# crystalis.net
KiCad netlist of a schematic drawn in EAGLE
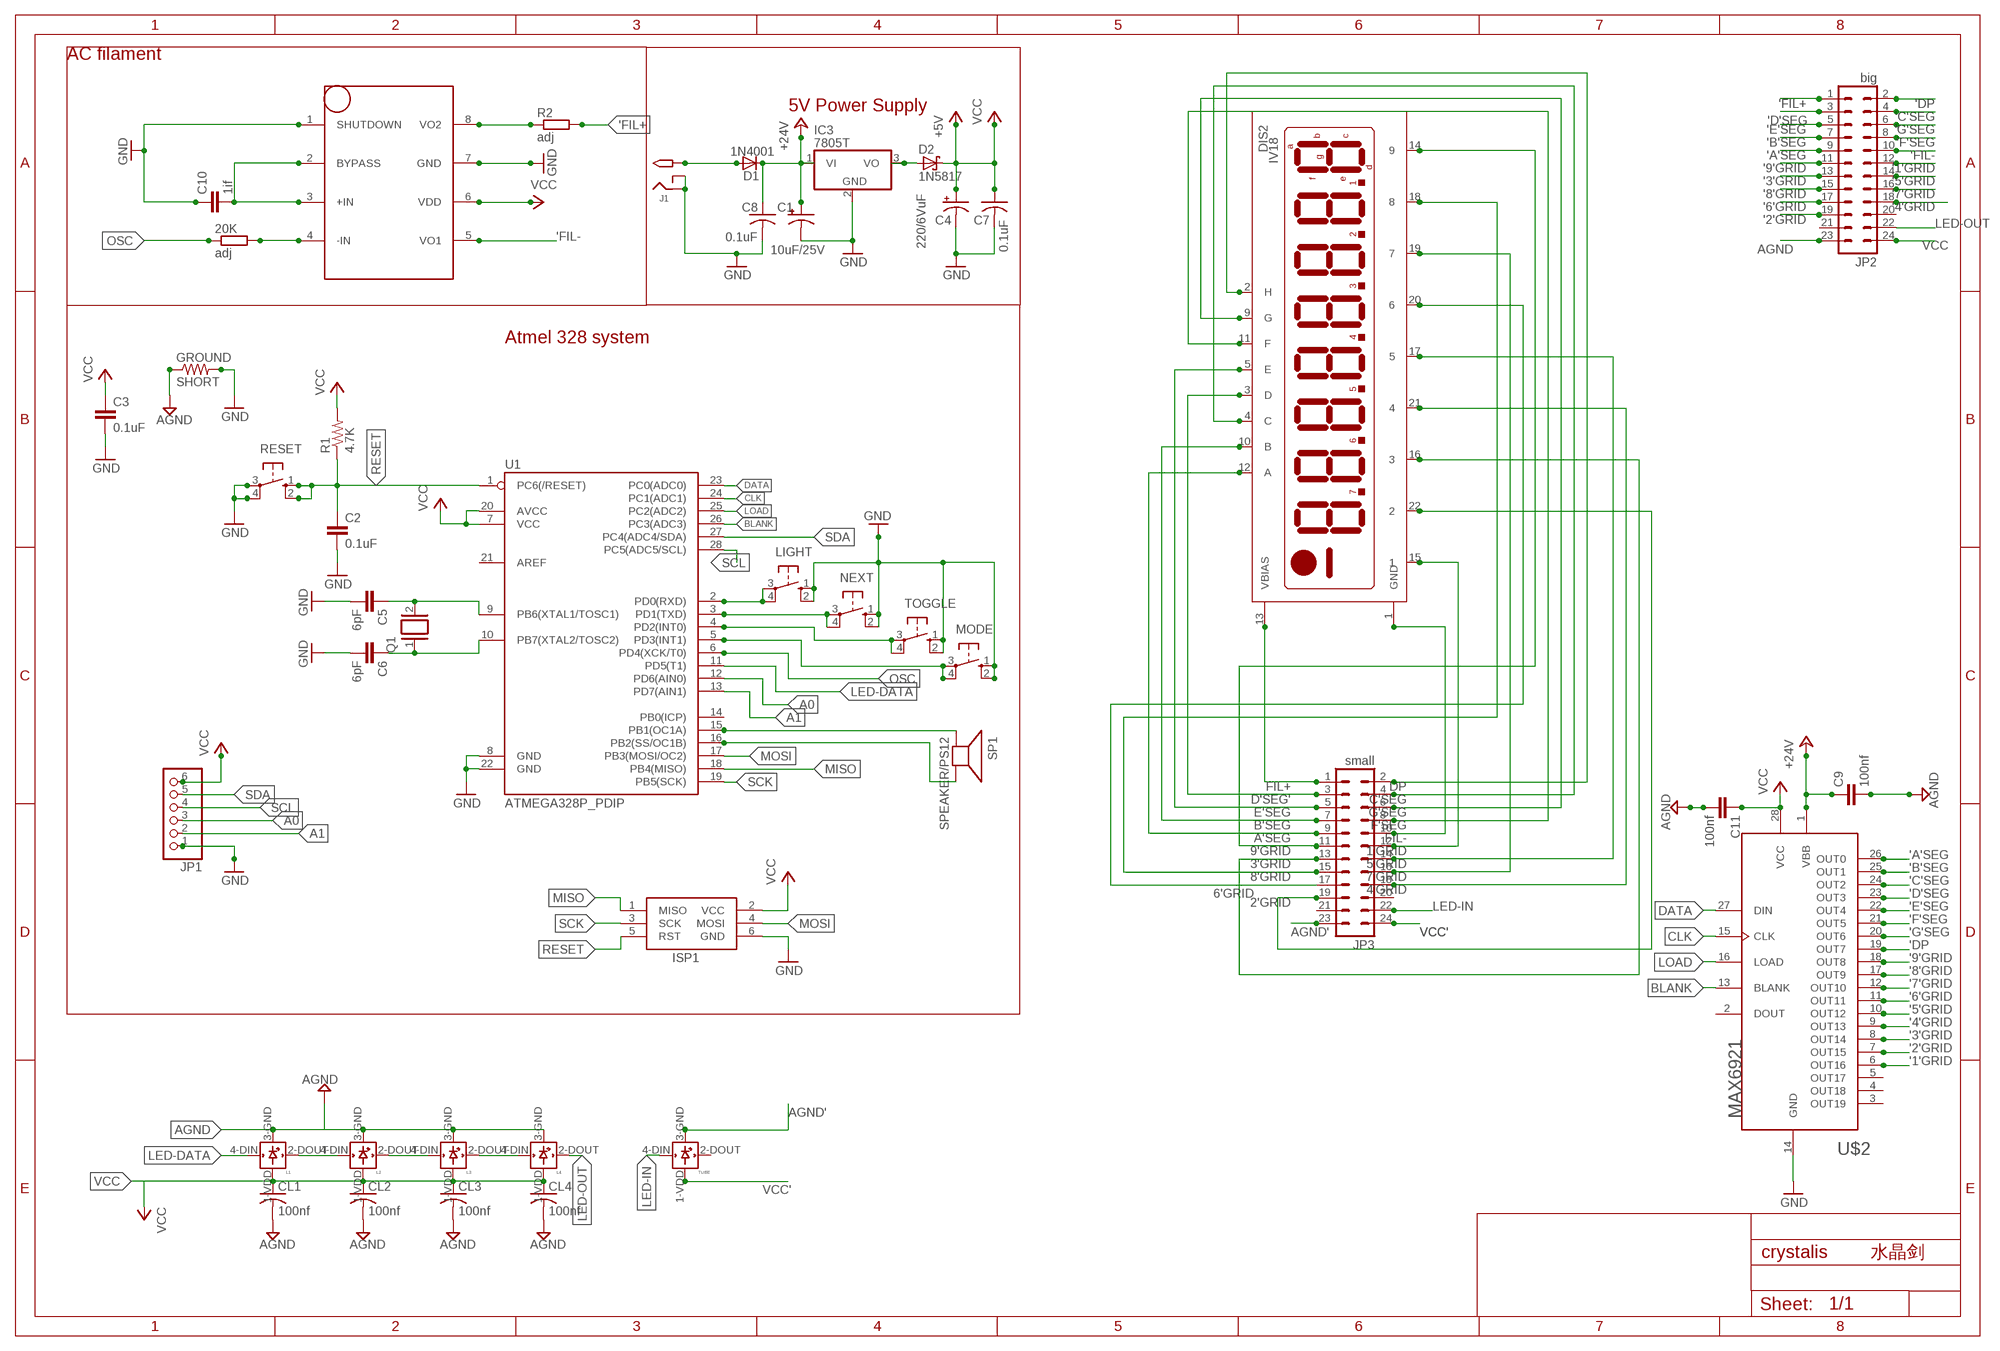
[diagram p0: schematic, sheet 1]

(export (version "E")
  (design (tool "Eeschema 10.0.6"))
  (components
    (comp (ref "20K")
      (value "adj")
      (footprint "eagle-import:0207_5V")
      (libsource (lib "eagle-import") (part "R-EU_0207/5V"))
    )
    (comp (ref "C1")
      (value "10uF/25V")
      (footprint "eagle-import:E2,5-6")
      (libsource (lib "eagle-import") (part "CPOL-USE2.5-6"))
    )
    (comp (ref "C2")
      (value "0.1uF")
      (footprint "eagle-import:C025-025X050")
      (libsource (lib "eagle-import") (part "C-EU025-025X050"))
    )
    (comp (ref "C3")
      (value "0.1uF")
      (footprint "eagle-import:C025-025X050")
      (libsource (lib "eagle-import") (part "C-EU025-025X050"))
    )
    (comp (ref "C4")
      (value "220/6VuF")
      (footprint "eagle-import:E2,5-6")
      (libsource (lib "eagle-import") (part "CPOL-USE2.5-6"))
    )
    (comp (ref "C5")
      (value "6pF")
      (footprint "eagle-import:C025-024X044")
      (libsource (lib "eagle-import") (part "C-EU025-024X044"))
    )
    (comp (ref "C6")
      (value "6pF")
      (footprint "eagle-import:C025-024X044")
      (libsource (lib "eagle-import") (part "C-EU025-024X044"))
    )
    (comp (ref "C7")
      (value "0.1uF")
      (footprint "eagle-import:C025-025X050")
      (libsource (lib "eagle-import") (part "C-US025-025X050"))
    )
    (comp (ref "C8")
      (value "0.1uF")
      (footprint "eagle-import:C025-025X050")
      (libsource (lib "eagle-import") (part "C-US025-025X050"))
    )
    (comp (ref "C9")
      (value "100nf")
      (footprint "eagle-import:C050-030X075")
      (libsource (lib "eagle-import") (part "C-EU050-030X075"))
    )
    (comp (ref "C10")
      (value "1if")
      (footprint "eagle-import:C025-030X050")
      (libsource (lib "eagle-import") (part "C-EU025-030X050"))
    )
    (comp (ref "C11")
      (value "100nf")
      (footprint "eagle-import:C050-030X075")
      (libsource (lib "eagle-import") (part "C-EU050-030X075"))
    )
    (comp (ref "CL1")
      (value "100nf")
      (footprint "eagle-import:C1206")
      (libsource (lib "eagle-import") (part "rcl_C-USC1206"))
    )
    (comp (ref "CL2")
      (value "100nf")
      (footprint "eagle-import:C1206")
      (libsource (lib "eagle-import") (part "rcl_C-USC1206"))
    )
    (comp (ref "CL3")
      (value "100nf")
      (footprint "eagle-import:C1206")
      (libsource (lib "eagle-import") (part "rcl_C-USC1206"))
    )
    (comp (ref "CL4")
      (value "100nf")
      (footprint "eagle-import:C1206")
      (libsource (lib "eagle-import") (part "rcl_C-USC1206"))
    )
    (comp (ref "D1")
      (value "1N4001")
      (footprint "eagle-import:DO41-10")
      (libsource (lib "eagle-import") (part "1N4004"))
    )
    (comp (ref "D2")
      (value "1N5817")
      (footprint "eagle-import:DO41-10")
      (libsource (lib "eagle-import") (part "SCHOTTKY-DIODEDO41"))
    )
    (comp (ref "DIS2")
      (value "IV18")
      (footprint "eagle-import:IV18")
      (libsource (lib "eagle-import") (part "IV18"))
    )
    (comp (ref "GROUND")
      (value "SHORT")
      (footprint "eagle-import:M1206")
      (libsource (lib "eagle-import") (part "R-US_M1206"))
    )
    (comp (ref "IC3")
      (value "7805T")
      (footprint "eagle-import:TO220H")
      (libsource (lib "eagle-import") (part "78T05"))
    )
    (comp (ref "ISP1")
      (value "AVRISP-6")
      (footprint "eagle-import:AVRISP")
      (libsource (lib "eagle-import") (part "AVRISP-6"))
    )
    (comp (ref "J1")
      (value "2.1MMJACK")
      (footprint "eagle-import:PJ-102A")
      (libsource (lib "eagle-import") (part "2.1MMJACK"))
    )
    (comp (ref "JP1")
      (value "PINHD-1X6")
      (footprint "eagle-import:1X06")
      (libsource (lib "eagle-import") (part "PINHD-1X6"))
    )
    (comp (ref "JP2")
      (value "big")
      (footprint "eagle-import:MA12-2")
      (libsource (lib "eagle-import") (part "MA12-2"))
    )
    (comp (ref "JP3")
      (value "small")
      (footprint "eagle-import:MA12-2")
      (libsource (lib "eagle-import") (part "MA12-2"))
    )
    (comp (ref "L1")
      (value "WS2812B")
      (footprint "eagle-import:WS2812B")
      (libsource (lib "eagle-import") (part "WS2812B"))
    )
    (comp (ref "L2")
      (value "WS2812B")
      (footprint "eagle-import:WS2812B")
      (libsource (lib "eagle-import") (part "WS2812B"))
    )
    (comp (ref "L3")
      (value "WS2812B")
      (footprint "eagle-import:WS2812B")
      (libsource (lib "eagle-import") (part "WS2812B"))
    )
    (comp (ref "L4")
      (value "WS2812B")
      (footprint "eagle-import:WS2812B")
      (libsource (lib "eagle-import") (part "WS2812B"))
    )
    (comp (ref "LIGHT")
      (value "40-XX")
      (footprint "eagle-import:B3F-40XX")
      (fields (field (name "MF") "OMRON COMPONENTS USA") (field (name "MPN") "B3F-4000"))
      (libsource (lib "eagle-import") (part "40-XX"))
    )
    (comp (ref "MODE")
      (value "40-XX")
      (footprint "eagle-import:B3F-40XX")
      (fields (field (name "MF") "OMRON COMPONENTS USA") (field (name "MPN") "B3F-4000"))
      (libsource (lib "eagle-import") (part "40-XX"))
    )
    (comp (ref "NEXT")
      (value "40-XX")
      (footprint "eagle-import:B3F-40XX")
      (fields (field (name "MF") "OMRON COMPONENTS USA") (field (name "MPN") "B3F-4000"))
      (libsource (lib "eagle-import") (part "40-XX"))
    )
    (comp (ref "Q1")
      (value "XTAL/S")
      (footprint "eagle-import:QS")
      (libsource (lib "eagle-import") (part "XTAL/S"))
    )
    (comp (ref "R1")
      (value "4.7K")
      (footprint "eagle-import:0309_12")
      (libsource (lib "eagle-import") (part "R-US_0309/12"))
    )
    (comp (ref "R2")
      (value "adj")
      (footprint "eagle-import:0207_5V")
      (libsource (lib "eagle-import") (part "R-EU_0207/5V"))
    )
    (comp (ref "RESET")
      (value "10-XX")
      (footprint "eagle-import:B3F-10XX")
      (fields (field (name "MPN") "B3F-1000"))
      (libsource (lib "eagle-import") (part "10-XX"))
    )
    (comp (ref "SP1")
      (value "SPEAKER/PS12")
      (footprint "eagle-import:PS12")
      (libsource (lib "eagle-import") (part "SPEAKER/PS12"))
    )
    (comp (ref "TOGGLE")
      (value "40-XX")
      (footprint "eagle-import:B3F-40XX")
      (fields (field (name "MF") "OMRON COMPONENTS USA") (field (name "MPN") "B3F-4000"))
      (libsource (lib "eagle-import") (part "40-XX"))
    )
    (comp (ref "TUBE")
      (value "WS2812B")
      (footprint "eagle-import:WS2812B")
      (libsource (lib "eagle-import") (part "WS2812B"))
    )
    (comp (ref "U$1")
      (value "LM4871")
      (footprint "eagle-import:SO08")
      (libsource (lib "eagle-import") (part "LM4871"))
    )
    (comp (ref "U$2")
      (value "MAX6921")
      (footprint "eagle-import:PLCC-S28")
      (libsource (lib "eagle-import") (part "MAX6921"))
    )
    (comp (ref "U1")
      (value "ATMEGA328P_PDIP")
      (footprint "eagle-import:DIL28-3")
      (libsource (lib "eagle-import") (part "ATMEGA328P_PDIP"))
    )
  )
  (nets
    (net (code "1") (name "'FIL+") (class "Default")
      (node (ref "JP2") (pin "1") (pinfunction "1_1") (pintype "passive"))
      (node (ref "R2") (pin "2") (pinfunction "2_2") (pintype "passive"))
    )
    (net (code "2") (name "+24V") (class "Default")
      (node (ref "C1") (pin "+") (pinfunction "+_+") (pintype "passive"))
      (node (ref "C8") (pin "1") (pinfunction "1_1") (pintype "passive"))
      (node (ref "C9") (pin "1") (pinfunction "1_1") (pintype "passive"))
      (node (ref "D1") (pin "C") (pinfunction "C_C") (pintype "passive"))
      (node (ref "IC3") (pin "1") (pinfunction "VI_1") (pintype "input"))
      (node (ref "U$2") (pin "1") (pinfunction "VBB_1") (pintype "power_in"))
    )
    (net (code "3") (name "/'1'GRID") (class "Default")
      (node (ref "JP2") (pin "12") (pinfunction "12_12") (pintype "passive"))
      (node (ref "U$2") (pin "6") (pinfunction "OUT16_6") (pintype "output"))
    )
    (net (code "4") (name "/'2'GRID") (class "Default")
      (node (ref "JP2") (pin "19") (pinfunction "19_19") (pintype "passive"))
      (node (ref "U$2") (pin "7") (pinfunction "OUT15_7") (pintype "output"))
    )
    (net (code "5") (name "/'3'GRID") (class "Default")
      (node (ref "JP2") (pin "13") (pinfunction "13_13") (pintype "passive"))
      (node (ref "U$2") (pin "8") (pinfunction "OUT14_8") (pintype "output"))
    )
    (net (code "6") (name "/'4'GRID") (class "Default")
      (node (ref "JP2") (pin "18") (pinfunction "18_18") (pintype "passive"))
      (node (ref "U$2") (pin "9") (pinfunction "OUT13_9") (pintype "output"))
    )
    (net (code "7") (name "/'5'GRID") (class "Default")
      (node (ref "JP2") (pin "14") (pinfunction "14_14") (pintype "passive"))
      (node (ref "U$2") (pin "10") (pinfunction "OUT12_10") (pintype "output"))
    )
    (net (code "8") (name "/'6'GRID") (class "Default")
      (node (ref "JP2") (pin "17") (pinfunction "17_17") (pintype "passive"))
      (node (ref "U$2") (pin "11") (pinfunction "OUT11_11") (pintype "output"))
    )
    (net (code "9") (name "/'7'GRID") (class "Default")
      (node (ref "JP2") (pin "16") (pinfunction "16_16") (pintype "passive"))
      (node (ref "U$2") (pin "12") (pinfunction "OUT10_12") (pintype "output"))
    )
    (net (code "10") (name "/'8'GRID") (class "Default")
      (node (ref "JP2") (pin "15") (pinfunction "15_15") (pintype "passive"))
      (node (ref "U$2") (pin "17") (pinfunction "OUT9_17") (pintype "output"))
    )
    (net (code "11") (name "/'9'GRID") (class "Default")
      (node (ref "JP2") (pin "11") (pinfunction "11_11") (pintype "passive"))
      (node (ref "U$2") (pin "18") (pinfunction "OUT8_18") (pintype "output"))
    )
    (net (code "12") (name "/'A'SEG") (class "Default")
      (node (ref "JP2") (pin "9") (pinfunction "9_9") (pintype "passive"))
      (node (ref "U$2") (pin "26") (pinfunction "OUT0_26") (pintype "output"))
    )
    (net (code "13") (name "/'B'SEG") (class "Default")
      (node (ref "JP2") (pin "7") (pinfunction "7_7") (pintype "passive"))
      (node (ref "U$2") (pin "25") (pinfunction "OUT1_25") (pintype "output"))
    )
    (net (code "14") (name "/'C'SEG") (class "Default")
      (node (ref "JP2") (pin "4") (pinfunction "4_4") (pintype "passive"))
      (node (ref "U$2") (pin "24") (pinfunction "OUT2_24") (pintype "output"))
    )
    (net (code "15") (name "/'D'SEG") (class "Default")
      (node (ref "JP2") (pin "3") (pinfunction "3_3") (pintype "passive"))
      (node (ref "U$2") (pin "23") (pinfunction "OUT3_23") (pintype "output"))
    )
    (net (code "16") (name "/'DP") (class "Default")
      (node (ref "JP2") (pin "2") (pinfunction "2_2") (pintype "passive"))
      (node (ref "U$2") (pin "19") (pinfunction "OUT7_19") (pintype "output"))
    )
    (net (code "17") (name "/'E'SEG") (class "Default")
      (node (ref "JP2") (pin "5") (pinfunction "5_5") (pintype "passive"))
      (node (ref "U$2") (pin "22") (pinfunction "OUT4_22") (pintype "output"))
    )
    (net (code "18") (name "/'F'SEG") (class "Default")
      (node (ref "JP2") (pin "8") (pinfunction "8_8") (pintype "passive"))
      (node (ref "U$2") (pin "21") (pinfunction "OUT5_21") (pintype "output"))
    )
    (net (code "19") (name "/'FIL-") (class "Default")
      (node (ref "JP2") (pin "10") (pinfunction "10_10") (pintype "passive"))
      (node (ref "U$1") (pin "5") (pinfunction "VO1_5") (pintype "bidirectional"))
    )
    (net (code "20") (name "/'G'SEG") (class "Default")
      (node (ref "JP2") (pin "6") (pinfunction "6_6") (pintype "passive"))
      (node (ref "U$2") (pin "20") (pinfunction "OUT6_20") (pintype "output"))
    )
    (net (code "21") (name "/1'GRID") (class "Default")
      (node (ref "DIS2") (pin "15") (pinfunction "1_15") (pintype "passive"))
      (node (ref "JP3") (pin "12") (pinfunction "12_12") (pintype "passive"))
    )
    (net (code "22") (name "/2'GRID") (class "Default")
      (node (ref "DIS2") (pin "22") (pinfunction "2_22") (pintype "passive"))
      (node (ref "JP3") (pin "19") (pinfunction "19_19") (pintype "passive"))
    )
    (net (code "23") (name "/3'GRID") (class "Default")
      (node (ref "DIS2") (pin "16") (pinfunction "3_16") (pintype "passive"))
      (node (ref "JP3") (pin "13") (pinfunction "13_13") (pintype "passive"))
    )
    (net (code "24") (name "/4'GRID") (class "Default")
      (node (ref "DIS2") (pin "21") (pinfunction "4_21") (pintype "passive"))
      (node (ref "JP3") (pin "18") (pinfunction "18_18") (pintype "passive"))
    )
    (net (code "25") (name "/5'GRID") (class "Default")
      (node (ref "DIS2") (pin "17") (pinfunction "5_17") (pintype "passive"))
      (node (ref "JP3") (pin "14") (pinfunction "14_14") (pintype "passive"))
    )
    (net (code "26") (name "/6'GRID") (class "Default")
      (node (ref "DIS2") (pin "20") (pinfunction "6_20") (pintype "passive"))
      (node (ref "JP3") (pin "17") (pinfunction "17_17") (pintype "passive"))
    )
    (net (code "27") (name "/7'GRID") (class "Default")
      (node (ref "DIS2") (pin "19") (pinfunction "7_19") (pintype "passive"))
      (node (ref "JP3") (pin "16") (pinfunction "16_16") (pintype "passive"))
    )
    (net (code "28") (name "/8'GRID") (class "Default")
      (node (ref "DIS2") (pin "18") (pinfunction "8_18") (pintype "passive"))
      (node (ref "JP3") (pin "15") (pinfunction "15_15") (pintype "passive"))
    )
    (net (code "29") (name "/9'GRID") (class "Default")
      (node (ref "DIS2") (pin "14") (pinfunction "9_14") (pintype "passive"))
      (node (ref "JP3") (pin "11") (pinfunction "11_11") (pintype "passive"))
    )
    (net (code "30") (name "/A'SEG") (class "Default")
      (node (ref "DIS2") (pin "12") (pinfunction "A_12") (pintype "passive"))
      (node (ref "JP3") (pin "9") (pinfunction "9_9") (pintype "passive"))
    )
    (net (code "31") (name "/AGND'") (class "Default")
      (node (ref "JP3") (pin "23") (pinfunction "23_23") (pintype "passive"))
      (node (ref "TUBE") (pin "3-GND") (pinfunction "GND_3-GND") (pintype "bidirectional"))
    )
    (net (code "32") (name "/B'SEG") (class "Default")
      (node (ref "DIS2") (pin "10") (pinfunction "B_10") (pintype "passive"))
      (node (ref "JP3") (pin "7") (pinfunction "7_7") (pintype "passive"))
    )
    (net (code "33") (name "/C'SEG") (class "Default")
      (node (ref "DIS2") (pin "4") (pinfunction "C_4") (pintype "passive"))
      (node (ref "JP3") (pin "4") (pinfunction "4_4") (pintype "passive"))
    )
    (net (code "34") (name "/D'SEG'") (class "Default")
      (node (ref "DIS2") (pin "3") (pinfunction "D_3") (pintype "passive"))
      (node (ref "JP3") (pin "3") (pinfunction "3_3") (pintype "passive"))
    )
    (net (code "35") (name "/DP") (class "Default")
      (node (ref "DIS2") (pin "2") (pinfunction "H_2") (pintype "passive"))
      (node (ref "JP3") (pin "2") (pinfunction "2_2") (pintype "passive"))
    )
    (net (code "36") (name "/E'SEG") (class "Default")
      (node (ref "DIS2") (pin "5") (pinfunction "E_5") (pintype "passive"))
      (node (ref "JP3") (pin "5") (pinfunction "5_5") (pintype "passive"))
    )
    (net (code "37") (name "/F'SEG") (class "Default")
      (node (ref "DIS2") (pin "11") (pinfunction "F_11") (pintype "passive"))
      (node (ref "JP3") (pin "8") (pinfunction "8_8") (pintype "passive"))
    )
    (net (code "38") (name "/FIL+") (class "Default")
      (node (ref "DIS2") (pin "13") (pinfunction "VBIAS_13") (pintype "power_in"))
      (node (ref "JP3") (pin "1") (pinfunction "1_1") (pintype "passive"))
    )
    (net (code "39") (name "/FIL-") (class "Default")
      (node (ref "DIS2") (pin "1") (pinfunction "GND_1") (pintype "power_in"))
      (node (ref "JP3") (pin "10") (pinfunction "10_10") (pintype "passive"))
    )
    (net (code "40") (name "/G'SEG") (class "Default")
      (node (ref "DIS2") (pin "9") (pinfunction "G_9") (pintype "passive"))
      (node (ref "JP3") (pin "6") (pinfunction "6_6") (pintype "passive"))
    )
    (net (code "41") (name "/VCC'") (class "Default")
      (node (ref "JP3") (pin "24") (pinfunction "24_24") (pintype "passive"))
      (node (ref "TUBE") (pin "1-VDD") (pinfunction "VDD_1-VDD") (pintype "bidirectional"))
    )
    (net (code "42") (name "A0") (class "Default")
      (node (ref "JP1") (pin "3") (pinfunction "3_3") (pintype "passive"))
      (node (ref "U1") (pin "12") (pinfunction "PD6(AIN0)_12") (pintype "bidirectional"))
    )
    (net (code "43") (name "A1") (class "Default")
      (node (ref "JP1") (pin "2") (pinfunction "2_2") (pintype "passive"))
      (node (ref "U1") (pin "13") (pinfunction "PD7(AIN1)_13") (pintype "bidirectional"))
    )
    (net (code "44") (name "AGND") (class "Default")
      (node (ref "C11") (pin "2") (pinfunction "2_2") (pintype "passive"))
      (node (ref "C9") (pin "2") (pinfunction "2_2") (pintype "passive"))
      (node (ref "CL1") (pin "2") (pinfunction "2_2") (pintype "passive"))
      (node (ref "CL2") (pin "2") (pinfunction "2_2") (pintype "passive"))
      (node (ref "CL3") (pin "2") (pinfunction "2_2") (pintype "passive"))
      (node (ref "CL4") (pin "2") (pinfunction "2_2") (pintype "passive"))
      (node (ref "GROUND") (pin "1") (pinfunction "1_1") (pintype "passive"))
      (node (ref "JP2") (pin "23") (pinfunction "23_23") (pintype "passive"))
      (node (ref "L1") (pin "3-GND") (pinfunction "GND_3-GND") (pintype "bidirectional"))
      (node (ref "L2") (pin "3-GND") (pinfunction "GND_3-GND") (pintype "bidirectional"))
      (node (ref "L3") (pin "3-GND") (pinfunction "GND_3-GND") (pintype "bidirectional"))
      (node (ref "L4") (pin "3-GND") (pinfunction "GND_3-GND") (pintype "bidirectional"))
    )
    (net (code "45") (name "BLANK") (class "Default")
      (node (ref "U$2") (pin "13") (pinfunction "BLANK_13") (pintype "input"))
      (node (ref "U1") (pin "26") (pinfunction "PC3(ADC3)_26") (pintype "bidirectional"))
    )
    (net (code "46") (name "CLK") (class "Default")
      (node (ref "U$2") (pin "15") (pinfunction "CLK_15") (pintype "input"))
      (node (ref "U1") (pin "24") (pinfunction "PC1(ADC1)_24") (pintype "bidirectional"))
    )
    (net (code "47") (name "DATA") (class "Default")
      (node (ref "U$2") (pin "27") (pinfunction "DIN_27") (pintype "input"))
      (node (ref "U1") (pin "23") (pinfunction "PC0(ADC0)_23") (pintype "bidirectional"))
    )
    (net (code "48") (name "GND") (class "Default")
      (node (ref "C1") (pin "-") (pinfunction "-_-") (pintype "passive"))
      (node (ref "C10") (pin "1") (pinfunction "1_1") (pintype "passive"))
      (node (ref "C2") (pin "2") (pinfunction "2_2") (pintype "passive"))
      (node (ref "C3") (pin "2") (pinfunction "2_2") (pintype "passive"))
      (node (ref "C4") (pin "-") (pinfunction "-_-") (pintype "passive"))
      (node (ref "C5") (pin "2") (pinfunction "2_2") (pintype "passive"))
      (node (ref "C6") (pin "2") (pinfunction "2_2") (pintype "passive"))
      (node (ref "C7") (pin "2") (pinfunction "2_2") (pintype "passive"))
      (node (ref "C8") (pin "2") (pinfunction "2_2") (pintype "passive"))
      (node (ref "GROUND") (pin "2") (pinfunction "2_2") (pintype "passive"))
      (node (ref "IC3") (pin "2") (pinfunction "GND_2") (pintype "passive"))
      (node (ref "ISP1") (pin "6") (pinfunction "GND_6") (pintype "power_in"))
      (node (ref "J1") (pin "RING") (pinfunction "RING_RING") (pintype "bidirectional"))
      (node (ref "J1") (pin "RING_SW") (pinfunction "RING_SW_RING_SW") (pintype "bidirectional"))
      (node (ref "JP1") (pin "1") (pinfunction "1_1") (pintype "passive"))
      (node (ref "LIGHT") (pin "1") (pinfunction "S_1") (pintype "passive"))
      (node (ref "LIGHT") (pin "2") (pinfunction "S1_2") (pintype "passive"))
      (node (ref "MODE") (pin "1") (pinfunction "S_1") (pintype "passive"))
      (node (ref "MODE") (pin "2") (pinfunction "S1_2") (pintype "passive"))
      (node (ref "NEXT") (pin "1") (pinfunction "S_1") (pintype "passive"))
      (node (ref "NEXT") (pin "2") (pinfunction "S1_2") (pintype "passive"))
      (node (ref "RESET") (pin "3") (pinfunction "P_3") (pintype "passive"))
      (node (ref "RESET") (pin "4") (pinfunction "P1_4") (pintype "passive"))
      (node (ref "TOGGLE") (pin "1") (pinfunction "S_1") (pintype "passive"))
      (node (ref "TOGGLE") (pin "2") (pinfunction "S1_2") (pintype "passive"))
      (node (ref "U$1") (pin "1") (pinfunction "SHUTDOWN_1") (pintype "bidirectional"))
      (node (ref "U$1") (pin "7") (pinfunction "GND_7") (pintype "bidirectional"))
      (node (ref "U$2") (pin "14") (pinfunction "GND_14") (pintype "power_in"))
      (node (ref "U1") (pin "22") (pinfunction "GND_22") (pintype "bidirectional"))
      (node (ref "U1") (pin "8") (pinfunction "GND_8") (pintype "bidirectional"))
    )
    (net (code "49") (name "LED-DATA") (class "Default")
      (node (ref "L1") (pin "4-DIN") (pinfunction "DIN_4-DIN") (pintype "input"))
      (node (ref "U1") (pin "11") (pinfunction "PD5(T1)_11") (pintype "bidirectional"))
    )
    (net (code "50") (name "LED-IN") (class "Default")
      (node (ref "JP3") (pin "22") (pinfunction "22_22") (pintype "passive"))
      (node (ref "TUBE") (pin "4-DIN") (pinfunction "DIN_4-DIN") (pintype "input"))
    )
    (net (code "51") (name "LED-OUT") (class "Default")
      (node (ref "JP2") (pin "22") (pinfunction "22_22") (pintype "passive"))
      (node (ref "L4") (pin "2-DOUT") (pinfunction "DOUT_2-DOUT") (pintype "output"))
    )
    (net (code "52") (name "LOAD") (class "Default")
      (node (ref "U$2") (pin "16") (pinfunction "LOAD_16") (pintype "input"))
      (node (ref "U1") (pin "25") (pinfunction "PC2(ADC2)_25") (pintype "bidirectional"))
    )
    (net (code "53") (name "MISO") (class "Default")
      (node (ref "ISP1") (pin "1") (pinfunction "MISO_1") (pintype "input"))
      (node (ref "U1") (pin "18") (pinfunction "PB4(MISO)_18") (pintype "bidirectional"))
    )
    (net (code "54") (name "MOSI") (class "Default")
      (node (ref "ISP1") (pin "4") (pinfunction "MOSI_4") (pintype "output"))
      (node (ref "U1") (pin "17") (pinfunction "PB3(MOSI/OC2)_17") (pintype "bidirectional"))
    )
    (net (code "55") (name "Net-(D1-PadA)") (class "Default")
      (node (ref "D1") (pin "A") (pinfunction "A_A") (pintype "passive"))
      (node (ref "J1") (pin "TIP") (pinfunction "TIP_TIP") (pintype "bidirectional"))
    )
    (net (code "56") (name "Net-(IC3-VO)") (class "Default")
      (node (ref "D2") (pin "A") (pinfunction "A_A") (pintype "passive"))
      (node (ref "IC3") (pin "3") (pinfunction "VO_3") (pintype "passive"))
    )
    (net (code "57") (name "Net-(L1-DOUT)") (class "Default")
      (node (ref "L1") (pin "2-DOUT") (pinfunction "DOUT_2-DOUT") (pintype "output"))
      (node (ref "L2") (pin "4-DIN") (pinfunction "DIN_4-DIN") (pintype "input"))
    )
    (net (code "58") (name "Net-(L2-DOUT)") (class "Default")
      (node (ref "L2") (pin "2-DOUT") (pinfunction "DOUT_2-DOUT") (pintype "output"))
      (node (ref "L3") (pin "4-DIN") (pinfunction "DIN_4-DIN") (pintype "input"))
    )
    (net (code "59") (name "Net-(L3-DOUT)") (class "Default")
      (node (ref "L3") (pin "2-DOUT") (pinfunction "DOUT_2-DOUT") (pintype "output"))
      (node (ref "L4") (pin "4-DIN") (pinfunction "DIN_4-DIN") (pintype "input"))
    )
    (net (code "60") (name "Net-(LIGHT-P)") (class "Default")
      (node (ref "LIGHT") (pin "3") (pinfunction "P_3") (pintype "passive"))
      (node (ref "LIGHT") (pin "4") (pinfunction "P1_4") (pintype "passive"))
      (node (ref "U1") (pin "2") (pinfunction "PD0(RXD)_2") (pintype "bidirectional"))
    )
    (net (code "61") (name "Net-(MODE-P)") (class "Default")
      (node (ref "MODE") (pin "3") (pinfunction "P_3") (pintype "passive"))
      (node (ref "MODE") (pin "4") (pinfunction "P1_4") (pintype "passive"))
      (node (ref "U1") (pin "5") (pinfunction "PD3(INT1)_5") (pintype "bidirectional"))
    )
    (net (code "62") (name "Net-(NEXT-P)") (class "Default")
      (node (ref "NEXT") (pin "3") (pinfunction "P_3") (pintype "passive"))
      (node (ref "NEXT") (pin "4") (pinfunction "P1_4") (pintype "passive"))
      (node (ref "U1") (pin "3") (pinfunction "PD1(TXD)_3") (pintype "bidirectional"))
    )
    (net (code "63") (name "Net-(SP1-+)") (class "Default")
      (node (ref "SP1") (pin "P$1") (pinfunction "+_P$1") (pintype "passive"))
      (node (ref "U1") (pin "15") (pinfunction "PB1(OC1A)_15") (pintype "bidirectional"))
    )
    (net (code "64") (name "Net-(SP1--)") (class "Default")
      (node (ref "SP1") (pin "P$2") (pinfunction "-_P$2") (pintype "passive"))
      (node (ref "U1") (pin "16") (pinfunction "PB2(SS/OC1B)_16") (pintype "bidirectional"))
    )
    (net (code "65") (name "Net-(TOGGLE-P)") (class "Default")
      (node (ref "TOGGLE") (pin "3") (pinfunction "P_3") (pintype "passive"))
      (node (ref "TOGGLE") (pin "4") (pinfunction "P1_4") (pintype "passive"))
      (node (ref "U1") (pin "4") (pinfunction "PD2(INT0)_4") (pintype "bidirectional"))
    )
    (net (code "66") (name "Net-(U$1-+IN)") (class "Default")
      (node (ref "C10") (pin "2") (pinfunction "2_2") (pintype "passive"))
      (node (ref "U$1") (pin "2") (pinfunction "BYPASS_2") (pintype "bidirectional"))
      (node (ref "U$1") (pin "3") (pinfunction "+IN_3") (pintype "bidirectional"))
    )
    (net (code "67") (name "Net-(U$1--IN)") (class "Default")
      (node (ref "20K") (pin "2") (pinfunction "2_2") (pintype "passive"))
      (node (ref "U$1") (pin "4") (pinfunction "-IN_4") (pintype "bidirectional"))
    )
    (net (code "68") (name "Net-(U$1-VO2)") (class "Default")
      (node (ref "R2") (pin "1") (pinfunction "1_1") (pintype "passive"))
      (node (ref "U$1") (pin "8") (pinfunction "VO2_8") (pintype "bidirectional"))
    )
    (net (code "69") (name "Net-(U1-PB6(XTAL1{slash}TOSC1))") (class "Default")
      (node (ref "C5") (pin "1") (pinfunction "1_1") (pintype "passive"))
      (node (ref "Q1") (pin "2") (pinfunction "2_2") (pintype "passive"))
      (node (ref "U1") (pin "9") (pinfunction "PB6(XTAL1/TOSC1)_9") (pintype "bidirectional"))
    )
    (net (code "70") (name "Net-(U1-PB7(XTAL2{slash}TOSC2))") (class "Default")
      (node (ref "C6") (pin "1") (pinfunction "1_1") (pintype "passive"))
      (node (ref "Q1") (pin "1") (pinfunction "1_1") (pintype "passive"))
      (node (ref "U1") (pin "10") (pinfunction "PB7(XTAL2/TOSC2)_10") (pintype "bidirectional"))
    )
    (net (code "71") (name "OSC") (class "Default")
      (node (ref "20K") (pin "1") (pinfunction "1_1") (pintype "passive"))
      (node (ref "U1") (pin "6") (pinfunction "PD4(XCK/T0)_6") (pintype "bidirectional"))
    )
    (net (code "72") (name "RESET") (class "Default")
      (node (ref "C2") (pin "1") (pinfunction "1_1") (pintype "passive"))
      (node (ref "ISP1") (pin "5") (pinfunction "RST_5") (pintype "output"))
      (node (ref "R1") (pin "1") (pinfunction "1_1") (pintype "passive"))
      (node (ref "RESET") (pin "1") (pinfunction "S_1") (pintype "passive"))
      (node (ref "RESET") (pin "2") (pinfunction "S1_2") (pintype "passive"))
      (node (ref "U1") (pin "1") (pinfunction "PC6(/RESET)_1") (pintype "bidirectional"))
    )
    (net (code "73") (name "SCK") (class "Default")
      (node (ref "ISP1") (pin "3") (pinfunction "SCK_3") (pintype "output"))
      (node (ref "U1") (pin "19") (pinfunction "PB5(SCK)_19") (pintype "bidirectional"))
    )
    (net (code "74") (name "SCL") (class "Default")
      (node (ref "JP1") (pin "4") (pinfunction "4_4") (pintype "passive"))
      (node (ref "U1") (pin "28") (pinfunction "PC5(ADC5/SCL)_28") (pintype "bidirectional"))
    )
    (net (code "75") (name "SDA") (class "Default")
      (node (ref "JP1") (pin "5") (pinfunction "5_5") (pintype "passive"))
      (node (ref "U1") (pin "27") (pinfunction "PC4(ADC4/SDA)_27") (pintype "bidirectional"))
    )
    (net (code "76") (name "VCC") (class "Default")
      (node (ref "C11") (pin "1") (pinfunction "1_1") (pintype "passive"))
      (node (ref "C3") (pin "1") (pinfunction "1_1") (pintype "passive"))
      (node (ref "C4") (pin "+") (pinfunction "+_+") (pintype "passive"))
      (node (ref "C7") (pin "1") (pinfunction "1_1") (pintype "passive"))
      (node (ref "CL1") (pin "1") (pinfunction "1_1") (pintype "passive"))
      (node (ref "CL2") (pin "1") (pinfunction "1_1") (pintype "passive"))
      (node (ref "CL3") (pin "1") (pinfunction "1_1") (pintype "passive"))
      (node (ref "CL4") (pin "1") (pinfunction "1_1") (pintype "passive"))
      (node (ref "D2") (pin "C") (pinfunction "C_C") (pintype "passive"))
      (node (ref "ISP1") (pin "2") (pinfunction "VCC_2") (pintype "power_in"))
      (node (ref "JP1") (pin "6") (pinfunction "6_6") (pintype "passive"))
      (node (ref "JP2") (pin "24") (pinfunction "24_24") (pintype "passive"))
      (node (ref "L1") (pin "1-VDD") (pinfunction "VDD_1-VDD") (pintype "bidirectional"))
      (node (ref "L2") (pin "1-VDD") (pinfunction "VDD_1-VDD") (pintype "bidirectional"))
      (node (ref "L3") (pin "1-VDD") (pinfunction "VDD_1-VDD") (pintype "bidirectional"))
      (node (ref "L4") (pin "1-VDD") (pinfunction "VDD_1-VDD") (pintype "bidirectional"))
      (node (ref "R1") (pin "2") (pinfunction "2_2") (pintype "passive"))
      (node (ref "U$1") (pin "6") (pinfunction "VDD_6") (pintype "bidirectional"))
      (node (ref "U$2") (pin "28") (pinfunction "VCC_28") (pintype "power_in"))
      (node (ref "U1") (pin "20") (pinfunction "AVCC_20") (pintype "bidirectional"))
      (node (ref "U1") (pin "7") (pinfunction "VCC_7") (pintype "bidirectional"))
    )
    (net (code "77") (name "unconnected-(JP2-Pad20)") (class "Default")
      (node (ref "JP2") (pin "20") (pinfunction "20_20") (pintype "passive"))
    )
    (net (code "78") (name "unconnected-(JP2-Pad21)") (class "Default")
      (node (ref "JP2") (pin "21") (pinfunction "21_21") (pintype "passive"))
    )
    (net (code "79") (name "unconnected-(JP3-Pad20)") (class "Default")
      (node (ref "JP3") (pin "20") (pinfunction "20_20") (pintype "passive"))
    )
    (net (code "80") (name "unconnected-(JP3-Pad21)") (class "Default")
      (node (ref "JP3") (pin "21") (pinfunction "21_21") (pintype "passive"))
    )
    (net (code "81") (name "unconnected-(TUBE-DOUT-Pad2-DOUT)") (class "Default")
      (node (ref "TUBE") (pin "2-DOUT") (pinfunction "DOUT_2-DOUT") (pintype "output"))
    )
    (net (code "82") (name "unconnected-(U$2-DOUT-Pad2)") (class "Default")
      (node (ref "U$2") (pin "2") (pinfunction "DOUT_2") (pintype "output"))
    )
    (net (code "83") (name "unconnected-(U$2-OUT17-Pad5)") (class "Default")
      (node (ref "U$2") (pin "5") (pinfunction "OUT17_5") (pintype "output"))
    )
    (net (code "84") (name "unconnected-(U$2-OUT18-Pad4)") (class "Default")
      (node (ref "U$2") (pin "4") (pinfunction "OUT18_4") (pintype "output"))
    )
    (net (code "85") (name "unconnected-(U$2-OUT19-Pad3)") (class "Default")
      (node (ref "U$2") (pin "3") (pinfunction "OUT19_3") (pintype "output"))
    )
    (net (code "86") (name "unconnected-(U1-AREF-Pad21)") (class "Default")
      (node (ref "U1") (pin "21") (pinfunction "AREF_21") (pintype "bidirectional"))
    )
    (net (code "87") (name "unconnected-(U1-PB0(ICP)-Pad14)") (class "Default")
      (node (ref "U1") (pin "14") (pinfunction "PB0(ICP)_14") (pintype "bidirectional"))
    )
  )
)
